# emat_igbt_switch_schmitt_trigger_40106.net
KiCad netlist of a schematic drawn in EAGLE
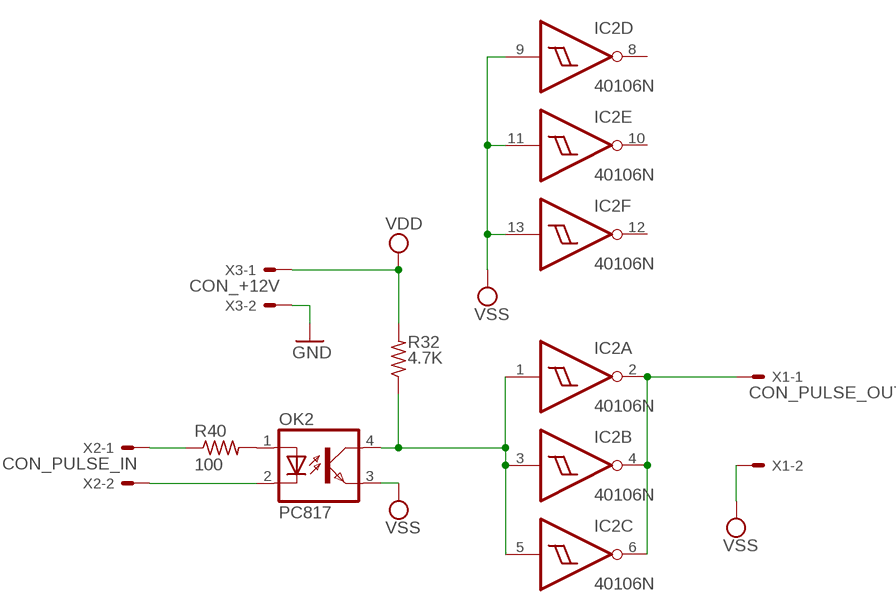
[diagram p0: schematic, sheet 1]

(export (version "E")
  (design (tool "Eeschema 10.0.6"))
  (components
    (comp (ref "IC2")
      (value "40106N")
      (footprint "eagle-import:DIL14")
      (libsource (lib "eagle-import") (part "40106N"))
    )
    (comp (ref "OK2")
      (value "PC817")
      (footprint "eagle-import:DIL04")
      (fields (field (name "MPN") "PC817X4J000F"))
      (libsource (lib "eagle-import") (part "PC817"))
    )
    (comp (ref "R32")
      (value "4.7K")
      (footprint "eagle-import:R1206")
      (libsource (lib "eagle-import") (part "R-US_R1206"))
    )
    (comp (ref "R40")
      (value "100")
      (footprint "eagle-import:R1206")
      (libsource (lib "eagle-import") (part "resistor_R-US_R1206"))
    )
    (comp (ref "X1")
      (value "CON_PULSE_OUT")
      (footprint "eagle-import:22-23-2021")
      (fields (field (name "MF") "MOLEX") (field (name "MPN") "22-23-2021"))
      (libsource (lib "eagle-import") (part "22-23-2021"))
    )
    (comp (ref "X2")
      (value "CON_PULSE_IN")
      (footprint "eagle-import:22-23-2021")
      (fields (field (name "MF") "MOLEX") (field (name "MPN") "22-23-2021"))
      (libsource (lib "eagle-import") (part "22-23-2021"))
    )
    (comp (ref "X3")
      (value "CON_+12V")
      (footprint "eagle-import:22-23-2021")
      (fields (field (name "MF") "MOLEX") (field (name "MPN") "22-23-2021"))
      (libsource (lib "eagle-import") (part "22-23-2021"))
    )
  )
  (nets
    (net (code "1") (name "GND") (class "Default")
      (node (ref "X3") (pin "2") (pinfunction "S_2") (pintype "passive"))
    )
    (net (code "2") (name "Net-(IC2A-I)") (class "Default")
      (node (ref "IC2") (pin "1") (pinfunction "I_1") (pintype "input"))
      (node (ref "IC2") (pin "3") (pinfunction "I_3") (pintype "input"))
      (node (ref "IC2") (pin "5") (pinfunction "I_5") (pintype "input"))
      (node (ref "OK2") (pin "4") (pinfunction "COL_4") (pintype "passive"))
      (node (ref "R32") (pin "1") (pinfunction "1_1") (pintype "passive"))
    )
    (net (code "3") (name "Net-(IC2A-O)") (class "Default")
      (node (ref "IC2") (pin "2") (pinfunction "O_2") (pintype "output"))
      (node (ref "IC2") (pin "4") (pinfunction "O_4") (pintype "output"))
      (node (ref "IC2") (pin "6") (pinfunction "O_6") (pintype "output"))
      (node (ref "X1") (pin "1") (pinfunction "S_1") (pintype "passive"))
    )
    (net (code "4") (name "Net-(OK2-A)") (class "Default")
      (node (ref "OK2") (pin "1") (pinfunction "A_1") (pintype "passive"))
      (node (ref "R40") (pin "2") (pinfunction "2_2") (pintype "passive"))
    )
    (net (code "5") (name "Net-(OK2-C)") (class "Default")
      (node (ref "OK2") (pin "2") (pinfunction "C_2") (pintype "passive"))
      (node (ref "X2") (pin "2") (pinfunction "S_2") (pintype "passive"))
    )
    (net (code "6") (name "Net-(X2A-S)") (class "Default")
      (node (ref "R40") (pin "1") (pinfunction "1_1") (pintype "passive"))
      (node (ref "X2") (pin "1") (pinfunction "S_1") (pintype "passive"))
    )
    (net (code "7") (name "VDD") (class "Default")
      (node (ref "R32") (pin "2") (pinfunction "2_2") (pintype "passive"))
      (node (ref "X3") (pin "1") (pinfunction "S_1") (pintype "passive"))
    )
    (net (code "8") (name "VSS") (class "Default")
      (node (ref "IC2") (pin "11") (pinfunction "I_11") (pintype "input"))
      (node (ref "IC2") (pin "13") (pinfunction "I_13") (pintype "input"))
      (node (ref "IC2") (pin "9") (pinfunction "I_9") (pintype "input"))
      (node (ref "OK2") (pin "3") (pinfunction "EMIT_3") (pintype "passive"))
      (node (ref "X1") (pin "2") (pinfunction "S_2") (pintype "passive"))
    )
    (net (code "9") (name "unconnected-(IC2D-O-Pad8)") (class "Default")
      (node (ref "IC2") (pin "8") (pinfunction "O_8") (pintype "output"))
    )
    (net (code "10") (name "unconnected-(IC2E-O-Pad10)") (class "Default")
      (node (ref "IC2") (pin "10") (pinfunction "O_10") (pintype "output"))
    )
    (net (code "11") (name "unconnected-(IC2F-O-Pad12)") (class "Default")
      (node (ref "IC2") (pin "12") (pinfunction "O_12") (pintype "output"))
    )
  )
)
